# PCA_0005_FULL_CB_Plugs_REV_B.net
KiCad netlist of a schematic drawn in Altium Designer
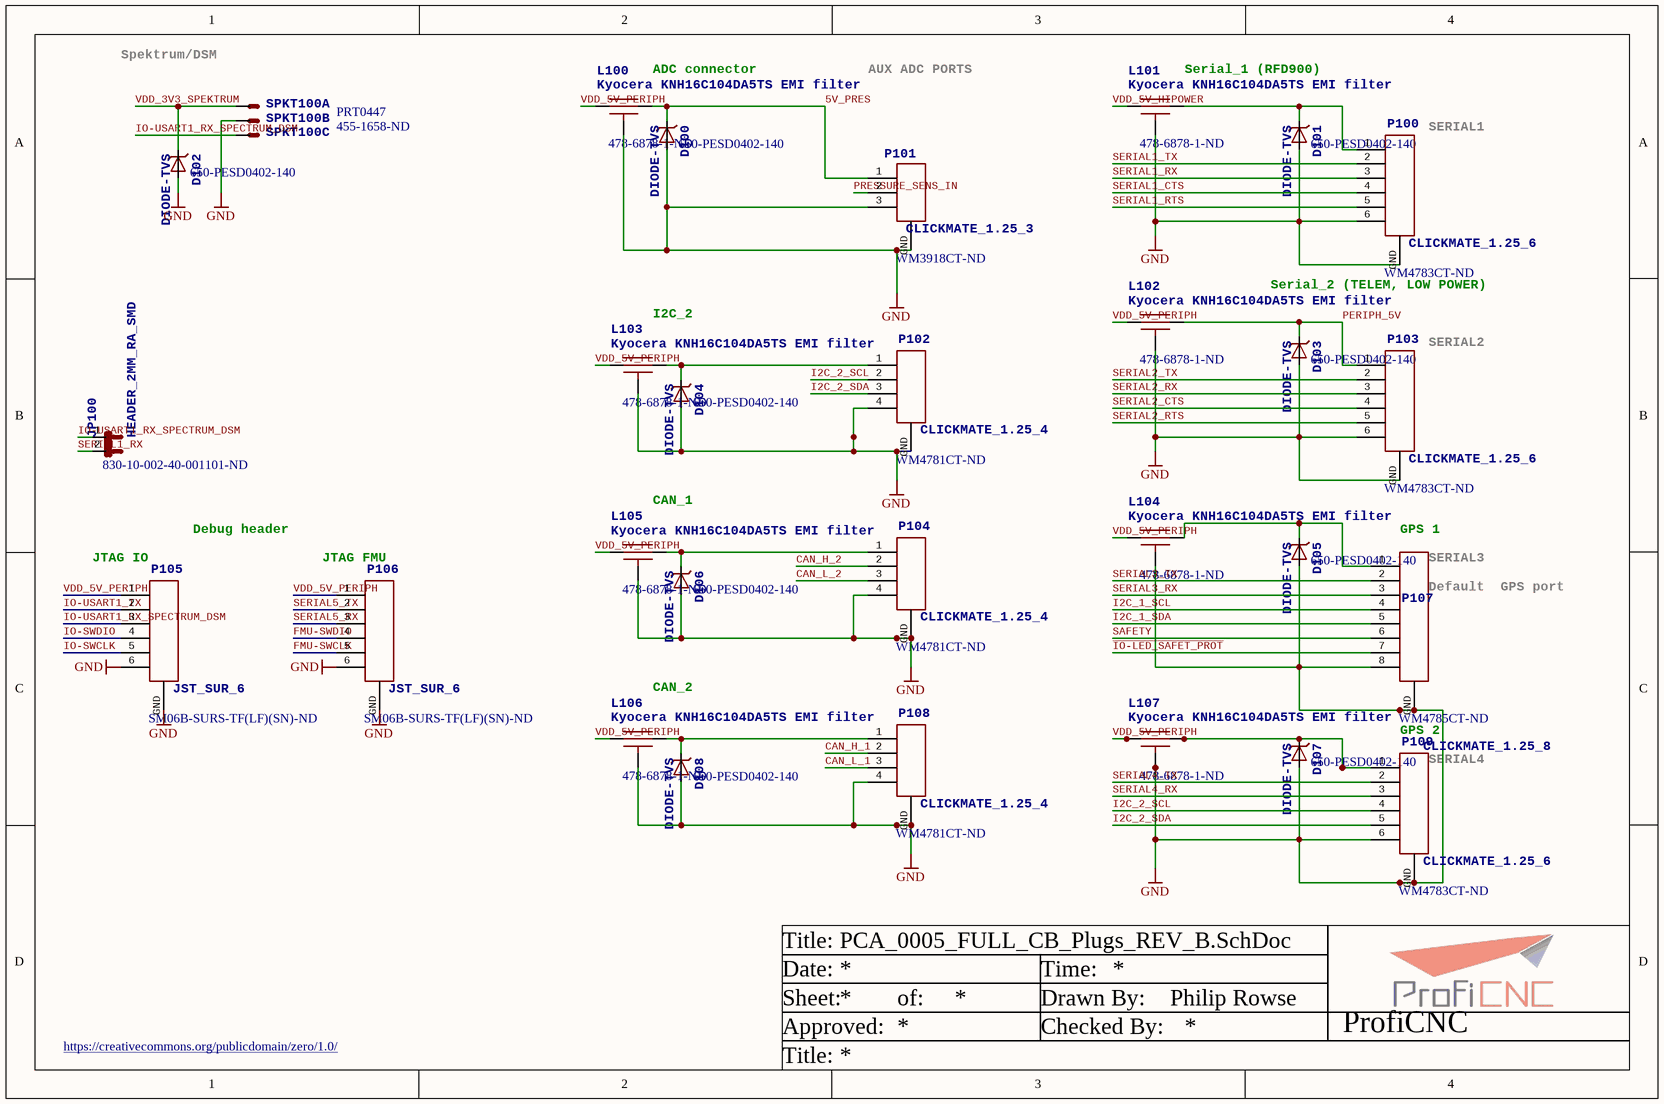
[diagram p0: PCA_0005_FULL_CB_Plugs_REV_B.SchDoc]

(export (version "E")
  (design (tool "Eeschema 10.0.6"))
  (components
    (comp (ref "D100")
      (value "DIODE-TVS")
      (footprint "0402-TVS")
      (description "Diode, TVS, 14VWM, 40VC, 0402, SMD")
      (fields
        (field (name "SUPPLIER PART NUMBER 1") "650-PESD0402-140")
        (field (name "3DR_PARTNO") "ECM0837")
      )
      (libsource (lib "PCA_0005_FULL_CB_REV_A") (part "DIODE-TVS"))
    )
    (comp (ref "D101")
      (value "DIODE-TVS")
      (footprint "0402-TVS")
      (description "Diode, TVS, 14VWM, 40VC, 0402, SMD")
      (fields
        (field (name "SUPPLIER PART NUMBER 1") "650-PESD0402-140")
        (field (name "3DR_PARTNO") "ECM0837")
      )
      (libsource (lib "PCA_0005_FULL_CB_REV_A") (part "DIODE-TVS"))
    )
    (comp (ref "D102")
      (value "DIODE-TVS")
      (footprint "0402-TVS")
      (description "Diode, TVS, 14VWM, 40VC, 0402, SMD")
      (fields
        (field (name "SUPPLIER PART NUMBER 1") "650-PESD0402-140")
        (field (name "3DR_PARTNO") "ECM0837")
      )
      (libsource (lib "PCA_0005_FULL_CB_REV_A") (part "DIODE-TVS"))
    )
    (comp (ref "D103")
      (value "DIODE-TVS")
      (footprint "0402-TVS")
      (description "Diode, TVS, 14VWM, 40VC, 0402, SMD")
      (fields
        (field (name "SUPPLIER PART NUMBER 1") "650-PESD0402-140")
        (field (name "3DR_PARTNO") "ECM0837")
      )
      (libsource (lib "PCA_0005_FULL_CB_REV_A") (part "DIODE-TVS"))
    )
    (comp (ref "D104")
      (value "DIODE-TVS")
      (footprint "0402-TVS")
      (description "Diode, TVS, 14VWM, 40VC, 0402, SMD")
      (fields
        (field (name "SUPPLIER PART NUMBER 1") "650-PESD0402-140")
        (field (name "3DR_PARTNO") "ECM0837")
      )
      (libsource (lib "PCA_0005_FULL_CB_REV_A") (part "DIODE-TVS"))
    )
    (comp (ref "D105")
      (value "DIODE-TVS")
      (footprint "0402-TVS")
      (description "Diode, TVS, 14VWM, 40VC, 0402, SMD")
      (fields
        (field (name "SUPPLIER PART NUMBER 1") "650-PESD0402-140")
        (field (name "3DR_PARTNO") "ECM0837")
      )
      (libsource (lib "PCA_0005_FULL_CB_REV_A") (part "DIODE-TVS"))
    )
    (comp (ref "D106")
      (value "DIODE-TVS")
      (footprint "0402-TVS")
      (description "Diode, TVS, 14VWM, 40VC, 0402, SMD")
      (fields
        (field (name "SUPPLIER PART NUMBER 1") "650-PESD0402-140")
        (field (name "3DR_PARTNO") "ECM0837")
      )
      (libsource (lib "PCA_0005_FULL_CB_REV_A") (part "DIODE-TVS"))
    )
    (comp (ref "D107")
      (value "DIODE-TVS")
      (footprint "0402-TVS")
      (description "Diode, TVS, 14VWM, 40VC, 0402, SMD")
      (fields
        (field (name "SUPPLIER PART NUMBER 1") "650-PESD0402-140")
        (field (name "3DR_PARTNO") "ECM0837")
      )
      (libsource (lib "PCA_0005_FULL_CB_REV_A") (part "DIODE-TVS"))
    )
    (comp (ref "D108")
      (value "DIODE-TVS")
      (footprint "0402-TVS")
      (description "Diode, TVS, 14VWM, 40VC, 0402, SMD")
      (fields
        (field (name "SUPPLIER PART NUMBER 1") "650-PESD0402-140")
        (field (name "3DR_PARTNO") "ECM0837")
      )
      (libsource (lib "PCA_0005_FULL_CB_REV_A") (part "DIODE-TVS"))
    )
    (comp (ref "JP100")
      (value "HEADER_2MM_RA_SMD")
      (footprint "HEADER_2MM_RA_2")
      (description "Connector, PCB, 2MM, 2Pos, R/A, SMD, Au")
      (fields
        (field (name "PARTNO") "830-10-002-40-001101")
        (field (name "SUPPLIER PART NUMBER 1") "830-10-002-40-001101-ND")
        (field (name "3DR_PARTNO") "PRT0437")
      )
      (libsource (lib "PCA_0005_FULL_CB_REV_A") (part "HEADER_2MM_RA_SMD"))
    )
    (comp (ref "L100")
      (value "Kyocera KNH16C104DA5TS EMI filter")
      (footprint "KYOCERA-KNH16-DA")
      (description "Capacitor, Filter, 0.1uF, 25V, 2A, 0603, SMD")
      (fields (field (name "SUPPLIER PART NUMBER 1") "478-6878-1-ND") (field (name "3DR_PARTNO") "ECM0719"))
      (libsource (lib "PCA_0005_FULL_CB_REV_A") (part "KNH16C104DA5TS"))
    )
    (comp (ref "L101")
      (value "Kyocera KNH16C104DA5TS EMI filter")
      (footprint "KYOCERA-KNH16-DA")
      (description "Capacitor, Filter, 0.1uF, 25V, 2A, 0603, SMD")
      (fields (field (name "SUPPLIER PART NUMBER 1") "478-6878-1-ND") (field (name "3DR_PARTNO") "ECM0719"))
      (libsource (lib "PCA_0005_FULL_CB_REV_A") (part "KNH16C104DA5TS"))
    )
    (comp (ref "L102")
      (value "Kyocera KNH16C104DA5TS EMI filter")
      (footprint "KYOCERA-KNH16-DA")
      (description "Capacitor, Filter, 0.1uF, 25V, 2A, 0603, SMD")
      (fields (field (name "SUPPLIER PART NUMBER 1") "478-6878-1-ND") (field (name "3DR_PARTNO") "ECM0719"))
      (libsource (lib "PCA_0005_FULL_CB_REV_A") (part "KNH16C104DA5TS"))
    )
    (comp (ref "L103")
      (value "Kyocera KNH16C104DA5TS EMI filter")
      (footprint "KYOCERA-KNH16-DA")
      (description "Capacitor, Filter, 0.1uF, 25V, 2A, 0603, SMD")
      (fields (field (name "SUPPLIER PART NUMBER 1") "478-6878-1-ND") (field (name "3DR_PARTNO") "ECM0719"))
      (libsource (lib "PCA_0005_FULL_CB_REV_A") (part "KNH16C104DA5TS"))
    )
    (comp (ref "L104")
      (value "Kyocera KNH16C104DA5TS EMI filter")
      (footprint "KYOCERA-KNH16-DA")
      (description "Capacitor, Filter, 0.1uF, 25V, 2A, 0603, SMD")
      (fields (field (name "SUPPLIER PART NUMBER 1") "478-6878-1-ND") (field (name "3DR_PARTNO") "ECM0719"))
      (libsource (lib "PCA_0005_FULL_CB_REV_A") (part "KNH16C104DA5TS"))
    )
    (comp (ref "L105")
      (value "Kyocera KNH16C104DA5TS EMI filter")
      (footprint "KYOCERA-KNH16-DA")
      (description "Capacitor, Filter, 0.1uF, 25V, 2A, 0603, SMD")
      (fields (field (name "SUPPLIER PART NUMBER 1") "478-6878-1-ND") (field (name "3DR_PARTNO") "ECM0719"))
      (libsource (lib "PCA_0005_FULL_CB_REV_A") (part "KNH16C104DA5TS"))
    )
    (comp (ref "L106")
      (value "Kyocera KNH16C104DA5TS EMI filter")
      (footprint "KYOCERA-KNH16-DA")
      (description "Capacitor, Filter, 0.1uF, 25V, 2A, 0603, SMD")
      (fields (field (name "SUPPLIER PART NUMBER 1") "478-6878-1-ND") (field (name "3DR_PARTNO") "ECM0719"))
      (libsource (lib "PCA_0005_FULL_CB_REV_A") (part "KNH16C104DA5TS"))
    )
    (comp (ref "L107")
      (value "Kyocera KNH16C104DA5TS EMI filter")
      (footprint "KYOCERA-KNH16-DA")
      (description "Capacitor, Filter, 0.1uF, 25V, 2A, 0603, SMD")
      (fields (field (name "SUPPLIER PART NUMBER 1") "478-6878-1-ND") (field (name "3DR_PARTNO") "ECM0719"))
      (libsource (lib "PCA_0005_FULL_CB_REV_A") (part "KNH16C104DA5TS"))
    )
    (comp (ref "P100")
      (value "CLICKMATE_1.25_6")
      (footprint "CLICKMATE_V6")
      (description "Connector, Rcpt, 6Pos, 1.25MM, W/B, VERT, SMD, Tin")
      (fields (field (name "SUPPLIER PART NUMBER 1") "WM4783CT-ND") (field (name "3DR_PARTNO") "PRT0439"))
      (libsource (lib "PCA_0005_FULL_CB_REV_A") (part "CLICKMATE_1.25_6"))
    )
    (comp (ref "P101")
      (value "CLICKMATE_1.25_3")
      (footprint "CLICKMATE_V3")
      (description "Connector, Rcpt,1.25MM,W/B,SGL,S/T,3CKT,SMD,Tin")
      (fields (field (name "SUPPLIER PART NUMBER 1") "WM3918CT-ND") (field (name "3DR_PARTNO") "PRT0440"))
      (libsource (lib "PCA_0005_FULL_CB_REV_A") (part "CLICKMATE_1.25_3"))
    )
    (comp (ref "P102")
      (value "CLICKMATE_1.25_4")
      (footprint "CLICKMATE_V4")
      (description "Connector, Rcpt, 4Pos, 1.25MM, W/B, VERT, SMD, Tin")
      (fields (field (name "SUPPLIER PART NUMBER 1") "WM4781CT-ND") (field (name "3DR_PARTNO") "PRT0441"))
      (libsource (lib "PCA_0005_FULL_CB_REV_A") (part "CLICKMATE_1.25_4"))
    )
    (comp (ref "P103")
      (value "CLICKMATE_1.25_6")
      (footprint "CLICKMATE_V6")
      (description "Connector, Rcpt, 6Pos, 1.25MM, W/B, VERT, SMD, Tin")
      (fields (field (name "SUPPLIER PART NUMBER 1") "WM4783CT-ND") (field (name "3DR_PARTNO") "PRT0439"))
      (libsource (lib "PCA_0005_FULL_CB_REV_A") (part "CLICKMATE_1.25_6"))
    )
    (comp (ref "P104")
      (value "CLICKMATE_1.25_4")
      (footprint "CLICKMATE_V4")
      (description "Connector, Rcpt, 4Pos, 1.25MM, W/B, VERT, SMD, Tin")
      (fields (field (name "SUPPLIER PART NUMBER 1") "WM4781CT-ND") (field (name "3DR_PARTNO") "PRT0441"))
      (libsource (lib "PCA_0005_FULL_CB_REV_A") (part "CLICKMATE_1.25_4"))
    )
    (comp (ref "P105")
      (value "JST_SUR_6")
      (footprint "JST_SUR_H6")
      (description "Connector, Header, 6Pos, .8mm IDC, R/A, SMD, Tin")
      (fields
        (field (name "SUPPLIER PART NUMBER 1") "SM06B-SURS-TF(LF)(SN)-ND")
        (field (name "3DR_PARTNO") "PRT0442")
      )
      (libsource (lib "PCA_0005_FULL_CB_REV_A") (part "JST_SUR_6"))
    )
    (comp (ref "P106")
      (value "JST_SUR_6")
      (footprint "JST_SUR_H6")
      (description "Connector, Header, 6Pos, .8mm IDC, R/A, SMD, Tin")
      (fields
        (field (name "SUPPLIER PART NUMBER 1") "SM06B-SURS-TF(LF)(SN)-ND")
        (field (name "3DR_PARTNO") "PRT0442")
      )
      (libsource (lib "PCA_0005_FULL_CB_REV_A") (part "JST_SUR_6"))
    )
    (comp (ref "P107")
      (value "CLICKMATE_1.25_8")
      (footprint "CLICKMATE_V8")
      (description "Connector, Rcpt, 8Pos, 1.25MM, W/B, VERT, SMD, Tin")
      (fields (field (name "SUPPLIER PART NUMBER 1") "WM4785CT-ND") (field (name "3DR_PARTNO") "PRT0443"))
      (libsource (lib "PCA_0005_FULL_CB_REV_A") (part "CLICKMATE_1.25_8"))
    )
    (comp (ref "P108")
      (value "CLICKMATE_1.25_4")
      (footprint "CLICKMATE_V4")
      (description "Connector, Rcpt, 4Pos, 1.25MM, W/B, VERT, SMD, Tin")
      (fields (field (name "SUPPLIER PART NUMBER 1") "WM4781CT-ND") (field (name "3DR_PARTNO") "PRT0441"))
      (libsource (lib "PCA_0005_FULL_CB_REV_A") (part "CLICKMATE_1.25_4"))
    )
    (comp (ref "P109")
      (value "CLICKMATE_1.25_6")
      (footprint "CLICKMATE_V6")
      (description "Connector, Rcpt, 6Pos, 1.25MM, W/B, VERT, SMD, Tin")
      (fields (field (name "SUPPLIER PART NUMBER 1") "WM4783CT-ND") (field (name "3DR_PARTNO") "PRT0439"))
      (libsource (lib "PCA_0005_FULL_CB_REV_A") (part "CLICKMATE_1.25_6"))
    )
    (comp (ref "SPKT100")
      (value "CONN_SPEKTRUM_RX-TH")
      (footprint "B3B-ZR")
      (description "Spektrum RX connector; JST ZH series S3B-ZR-SM4A-TF")
      (fields
        (field (name "PARTNO") "B3B-ZR(LF)(SN)")
        (field (name "3DR_PARTNO") "PRT0447")
        (field (name "SUPPLIER PART NUMBER 1") "455-1658-ND")
      )
      (libsource (lib "PCA_0005_FULL_CB_REV_A") (part "CONN_SPEKTRUM_RX-TH"))
    )
  )
  (nets
    (net (code "1") (name "/5V_PRES") (class "Default")
      (node (ref "D100") (pin "C") (pinfunction "C_C") (pintype "passive"))
      (node (ref "L100") (pin "P$2") (pinfunction "P$2_P$2") (pintype "passive"))
      (node (ref "P101") (pin "1") (pinfunction "1_1") (pintype "passive"))
    )
    (net (code "2") (name "/CAN_H_1") (class "Default")
      (node (ref "P108") (pin "2") (pinfunction "2_2") (pintype "passive"))
    )
    (net (code "3") (name "/CAN_H_2") (class "Default")
      (node (ref "P104") (pin "2") (pinfunction "2_2") (pintype "passive"))
    )
    (net (code "4") (name "/CAN_L_1") (class "Default")
      (node (ref "P108") (pin "3") (pinfunction "3_3") (pintype "passive"))
    )
    (net (code "5") (name "/CAN_L_2") (class "Default")
      (node (ref "P104") (pin "3") (pinfunction "3_3") (pintype "passive"))
    )
    (net (code "6") (name "/FMU-SWCLK") (class "Default")
      (node (ref "P106") (pin "5") (pinfunction "5_5") (pintype "passive"))
    )
    (net (code "7") (name "/FMU-SWDIO") (class "Default")
      (node (ref "P106") (pin "4") (pinfunction "4_4") (pintype "passive"))
    )
    (net (code "8") (name "/I2C_1_SCL") (class "Default")
      (node (ref "P107") (pin "4") (pinfunction "4_4") (pintype "passive"))
    )
    (net (code "9") (name "/I2C_1_SDA") (class "Default")
      (node (ref "P107") (pin "5") (pinfunction "5_5") (pintype "passive"))
    )
    (net (code "10") (name "/I2C_2_SCL") (class "Default")
      (node (ref "P102") (pin "2") (pinfunction "2_2") (pintype "passive"))
      (node (ref "P109") (pin "4") (pinfunction "4_4") (pintype "passive"))
    )
    (net (code "11") (name "/I2C_2_SDA") (class "Default")
      (node (ref "P102") (pin "3") (pinfunction "3_3") (pintype "passive"))
      (node (ref "P109") (pin "5") (pinfunction "5_5") (pintype "passive"))
    )
    (net (code "12") (name "/IO-SWCLK") (class "Default")
      (node (ref "P105") (pin "5") (pinfunction "5_5") (pintype "passive"))
    )
    (net (code "13") (name "/IO-SWDIO") (class "Default")
      (node (ref "P105") (pin "4") (pinfunction "4_4") (pintype "passive"))
    )
    (net (code "14") (name "/IO-USART1_RX_SPECTRUM_DSM") (class "Default")
      (node (ref "JP100") (pin "1") (pinfunction "1_1") (pintype "passive"))
      (node (ref "P105") (pin "3") (pinfunction "3_3") (pintype "passive"))
      (node (ref "SPKT100") (pin "1") (pinfunction "S_1") (pintype "passive"))
    )
    (net (code "15") (name "/IO-USART1_TX") (class "Default")
      (node (ref "P105") (pin "2") (pinfunction "2_2") (pintype "passive"))
    )
    (net (code "16") (name "/PERIPH_5V") (class "Default")
      (node (ref "D103") (pin "C") (pinfunction "C_C") (pintype "passive"))
      (node (ref "L102") (pin "P$2") (pinfunction "P$2_P$2") (pintype "passive"))
      (node (ref "P103") (pin "1") (pinfunction "1_1") (pintype "passive"))
    )
    (net (code "17") (name "/PRESSURE_SENS_IN") (class "Default")
      (node (ref "P101") (pin "2") (pinfunction "2_2") (pintype "passive"))
    )
    (net (code "18") (name "/SAFETY") (class "Default")
      (node (ref "P107") (pin "6") (pinfunction "6_6") (pintype "passive"))
    )
    (net (code "19") (name "/SERIAL1_CTS") (class "Default")
      (node (ref "P100") (pin "4") (pinfunction "4_4") (pintype "passive"))
    )
    (net (code "20") (name "/SERIAL1_RTS") (class "Default")
      (node (ref "P100") (pin "5") (pinfunction "5_5") (pintype "passive"))
    )
    (net (code "21") (name "/SERIAL1_RX") (class "Default")
      (node (ref "JP100") (pin "2") (pinfunction "2_2") (pintype "passive"))
      (node (ref "P100") (pin "3") (pinfunction "3_3") (pintype "passive"))
    )
    (net (code "22") (name "/SERIAL1_TX") (class "Default")
      (node (ref "P100") (pin "2") (pinfunction "2_2") (pintype "passive"))
    )
    (net (code "23") (name "/SERIAL2_CTS") (class "Default")
      (node (ref "P103") (pin "4") (pinfunction "4_4") (pintype "passive"))
    )
    (net (code "24") (name "/SERIAL2_RTS") (class "Default")
      (node (ref "P103") (pin "5") (pinfunction "5_5") (pintype "passive"))
    )
    (net (code "25") (name "/SERIAL2_RX") (class "Default")
      (node (ref "P103") (pin "3") (pinfunction "3_3") (pintype "passive"))
    )
    (net (code "26") (name "/SERIAL2_TX") (class "Default")
      (node (ref "P103") (pin "2") (pinfunction "2_2") (pintype "passive"))
    )
    (net (code "27") (name "/SERIAL3_RX") (class "Default")
      (node (ref "P107") (pin "3") (pinfunction "3_3") (pintype "passive"))
    )
    (net (code "28") (name "/SERIAL3_TX") (class "Default")
      (node (ref "P107") (pin "2") (pinfunction "2_2") (pintype "passive"))
    )
    (net (code "29") (name "/SERIAL4_RX") (class "Default")
      (node (ref "P109") (pin "3") (pinfunction "3_3") (pintype "passive"))
    )
    (net (code "30") (name "/SERIAL4_TX") (class "Default")
      (node (ref "P109") (pin "2") (pinfunction "2_2") (pintype "passive"))
    )
    (net (code "31") (name "/SERIAL5_RX") (class "Default")
      (node (ref "P106") (pin "3") (pinfunction "3_3") (pintype "passive"))
    )
    (net (code "32") (name "/SERIAL5_TX") (class "Default")
      (node (ref "P106") (pin "2") (pinfunction "2_2") (pintype "passive"))
    )
    (net (code "33") (name "/VDD_3V3_SPEKTRUM") (class "Default")
      (node (ref "D102") (pin "C") (pinfunction "C_C") (pintype "passive"))
      (node (ref "SPKT100") (pin "3") (pinfunction "S_3") (pintype "passive"))
    )
    (net (code "34") (name "/VDD_5V_HIPOWER") (class "Default")
      (node (ref "L101") (pin "P$1") (pinfunction "P$1_P$1") (pintype "passive"))
    )
    (net (code "35") (name "/VDD_5V_PERIPH") (class "Default")
      (node (ref "L100") (pin "P$1") (pinfunction "P$1_P$1") (pintype "passive"))
      (node (ref "L102") (pin "P$1") (pinfunction "P$1_P$1") (pintype "passive"))
      (node (ref "L103") (pin "P$1") (pinfunction "P$1_P$1") (pintype "passive"))
      (node (ref "L104") (pin "P$1") (pinfunction "P$1_P$1") (pintype "passive"))
      (node (ref "L105") (pin "P$1") (pinfunction "P$1_P$1") (pintype "passive"))
      (node (ref "L106") (pin "P$1") (pinfunction "P$1_P$1") (pintype "passive"))
      (node (ref "L107") (pin "P$1") (pinfunction "P$1_P$1") (pintype "passive"))
      (node (ref "P105") (pin "1") (pinfunction "1_1") (pintype "passive"))
      (node (ref "P106") (pin "1") (pinfunction "1_1") (pintype "passive"))
    )
    (net (code "36") (name "/~{IO-LED_SAFET_PROT}") (class "Default")
      (node (ref "P107") (pin "7") (pinfunction "7_7") (pintype "passive"))
    )
    (net (code "37") (name "GND") (class "Default")
      (node (ref "D100") (pin "A") (pinfunction "A_A") (pintype "passive"))
      (node (ref "D101") (pin "A") (pinfunction "A_A") (pintype "passive"))
      (node (ref "D102") (pin "A") (pinfunction "A_A") (pintype "passive"))
      (node (ref "D103") (pin "A") (pinfunction "A_A") (pintype "passive"))
      (node (ref "D104") (pin "A") (pinfunction "A_A") (pintype "passive"))
      (node (ref "D105") (pin "A") (pinfunction "A_A") (pintype "passive"))
      (node (ref "D106") (pin "A") (pinfunction "A_A") (pintype "passive"))
      (node (ref "D107") (pin "A") (pinfunction "A_A") (pintype "passive"))
      (node (ref "D108") (pin "A") (pinfunction "A_A") (pintype "passive"))
      (node (ref "L100") (pin "GND") (pinfunction "GND_GND") (pintype "passive"))
      (node (ref "L101") (pin "GND") (pinfunction "GND_GND") (pintype "passive"))
      (node (ref "L102") (pin "GND") (pinfunction "GND_GND") (pintype "passive"))
      (node (ref "L103") (pin "GND") (pinfunction "GND_GND") (pintype "passive"))
      (node (ref "L104") (pin "GND") (pinfunction "GND_GND") (pintype "passive"))
      (node (ref "L105") (pin "GND") (pinfunction "GND_GND") (pintype "passive"))
      (node (ref "L106") (pin "GND") (pinfunction "GND_GND") (pintype "passive"))
      (node (ref "L107") (pin "GND") (pinfunction "GND_GND") (pintype "passive"))
      (node (ref "P100") (pin "6") (pinfunction "6_6") (pintype "passive"))
      (node (ref "P100") (pin "GND") (pinfunction "GND_GND") (pintype "passive"))
      (node (ref "P101") (pin "3") (pinfunction "3_3") (pintype "passive"))
      (node (ref "P101") (pin "GND") (pinfunction "GND_GND") (pintype "passive"))
      (node (ref "P102") (pin "4") (pinfunction "4_4") (pintype "passive"))
      (node (ref "P102") (pin "GND") (pinfunction "GND_GND") (pintype "passive"))
      (node (ref "P103") (pin "6") (pinfunction "6_6") (pintype "passive"))
      (node (ref "P103") (pin "GND") (pinfunction "GND_GND") (pintype "passive"))
      (node (ref "P104") (pin "4") (pinfunction "4_4") (pintype "passive"))
      (node (ref "P104") (pin "GND") (pinfunction "GND_GND") (pintype "passive"))
      (node (ref "P105") (pin "6") (pinfunction "6_6") (pintype "passive"))
      (node (ref "P105") (pin "GND") (pinfunction "GND_GND") (pintype "passive"))
      (node (ref "P106") (pin "6") (pinfunction "6_6") (pintype "passive"))
      (node (ref "P106") (pin "GND") (pinfunction "GND_GND") (pintype "passive"))
      (node (ref "P107") (pin "8") (pinfunction "8_8") (pintype "passive"))
      (node (ref "P107") (pin "GND") (pinfunction "GND_GND") (pintype "passive"))
      (node (ref "P108") (pin "4") (pinfunction "4_4") (pintype "passive"))
      (node (ref "P108") (pin "GND") (pinfunction "GND_GND") (pintype "passive"))
      (node (ref "P109") (pin "6") (pinfunction "6_6") (pintype "passive"))
      (node (ref "P109") (pin "GND") (pinfunction "GND_GND") (pintype "passive"))
      (node (ref "SPKT100") (pin "2") (pinfunction "S_2") (pintype "passive"))
    )
    (net (code "38") (name "Net-(D101-PadC)") (class "Default")
      (node (ref "D101") (pin "C") (pinfunction "C_C") (pintype "passive"))
      (node (ref "L101") (pin "P$2") (pinfunction "P$2_P$2") (pintype "passive"))
      (node (ref "P100") (pin "1") (pinfunction "1_1") (pintype "passive"))
    )
    (net (code "39") (name "Net-(D104-PadC)") (class "Default")
      (node (ref "D104") (pin "C") (pinfunction "C_C") (pintype "passive"))
      (node (ref "L103") (pin "P$2") (pinfunction "P$2_P$2") (pintype "passive"))
      (node (ref "P102") (pin "1") (pinfunction "1_1") (pintype "passive"))
    )
    (net (code "40") (name "Net-(D105-PadC)") (class "Default")
      (node (ref "D105") (pin "C") (pinfunction "C_C") (pintype "passive"))
      (node (ref "L104") (pin "P$2") (pinfunction "P$2_P$2") (pintype "passive"))
      (node (ref "P107") (pin "1") (pinfunction "1_1") (pintype "passive"))
    )
    (net (code "41") (name "Net-(D106-PadC)") (class "Default")
      (node (ref "D106") (pin "C") (pinfunction "C_C") (pintype "passive"))
      (node (ref "L105") (pin "P$2") (pinfunction "P$2_P$2") (pintype "passive"))
      (node (ref "P104") (pin "1") (pinfunction "1_1") (pintype "passive"))
    )
    (net (code "42") (name "Net-(D107-PadC)") (class "Default")
      (node (ref "D107") (pin "C") (pinfunction "C_C") (pintype "passive"))
      (node (ref "L107") (pin "P$2") (pinfunction "P$2_P$2") (pintype "passive"))
      (node (ref "P109") (pin "1") (pinfunction "1_1") (pintype "passive"))
    )
    (net (code "43") (name "Net-(D108-PadC)") (class "Default")
      (node (ref "D108") (pin "C") (pinfunction "C_C") (pintype "passive"))
      (node (ref "L106") (pin "P$2") (pinfunction "P$2_P$2") (pintype "passive"))
      (node (ref "P108") (pin "1") (pinfunction "1_1") (pintype "passive"))
    )
  )
)
